# ProPrj_Usb_Hub_2026-05-05.net
KiCad netlist of a schematic drawn in EasyEDA Pro
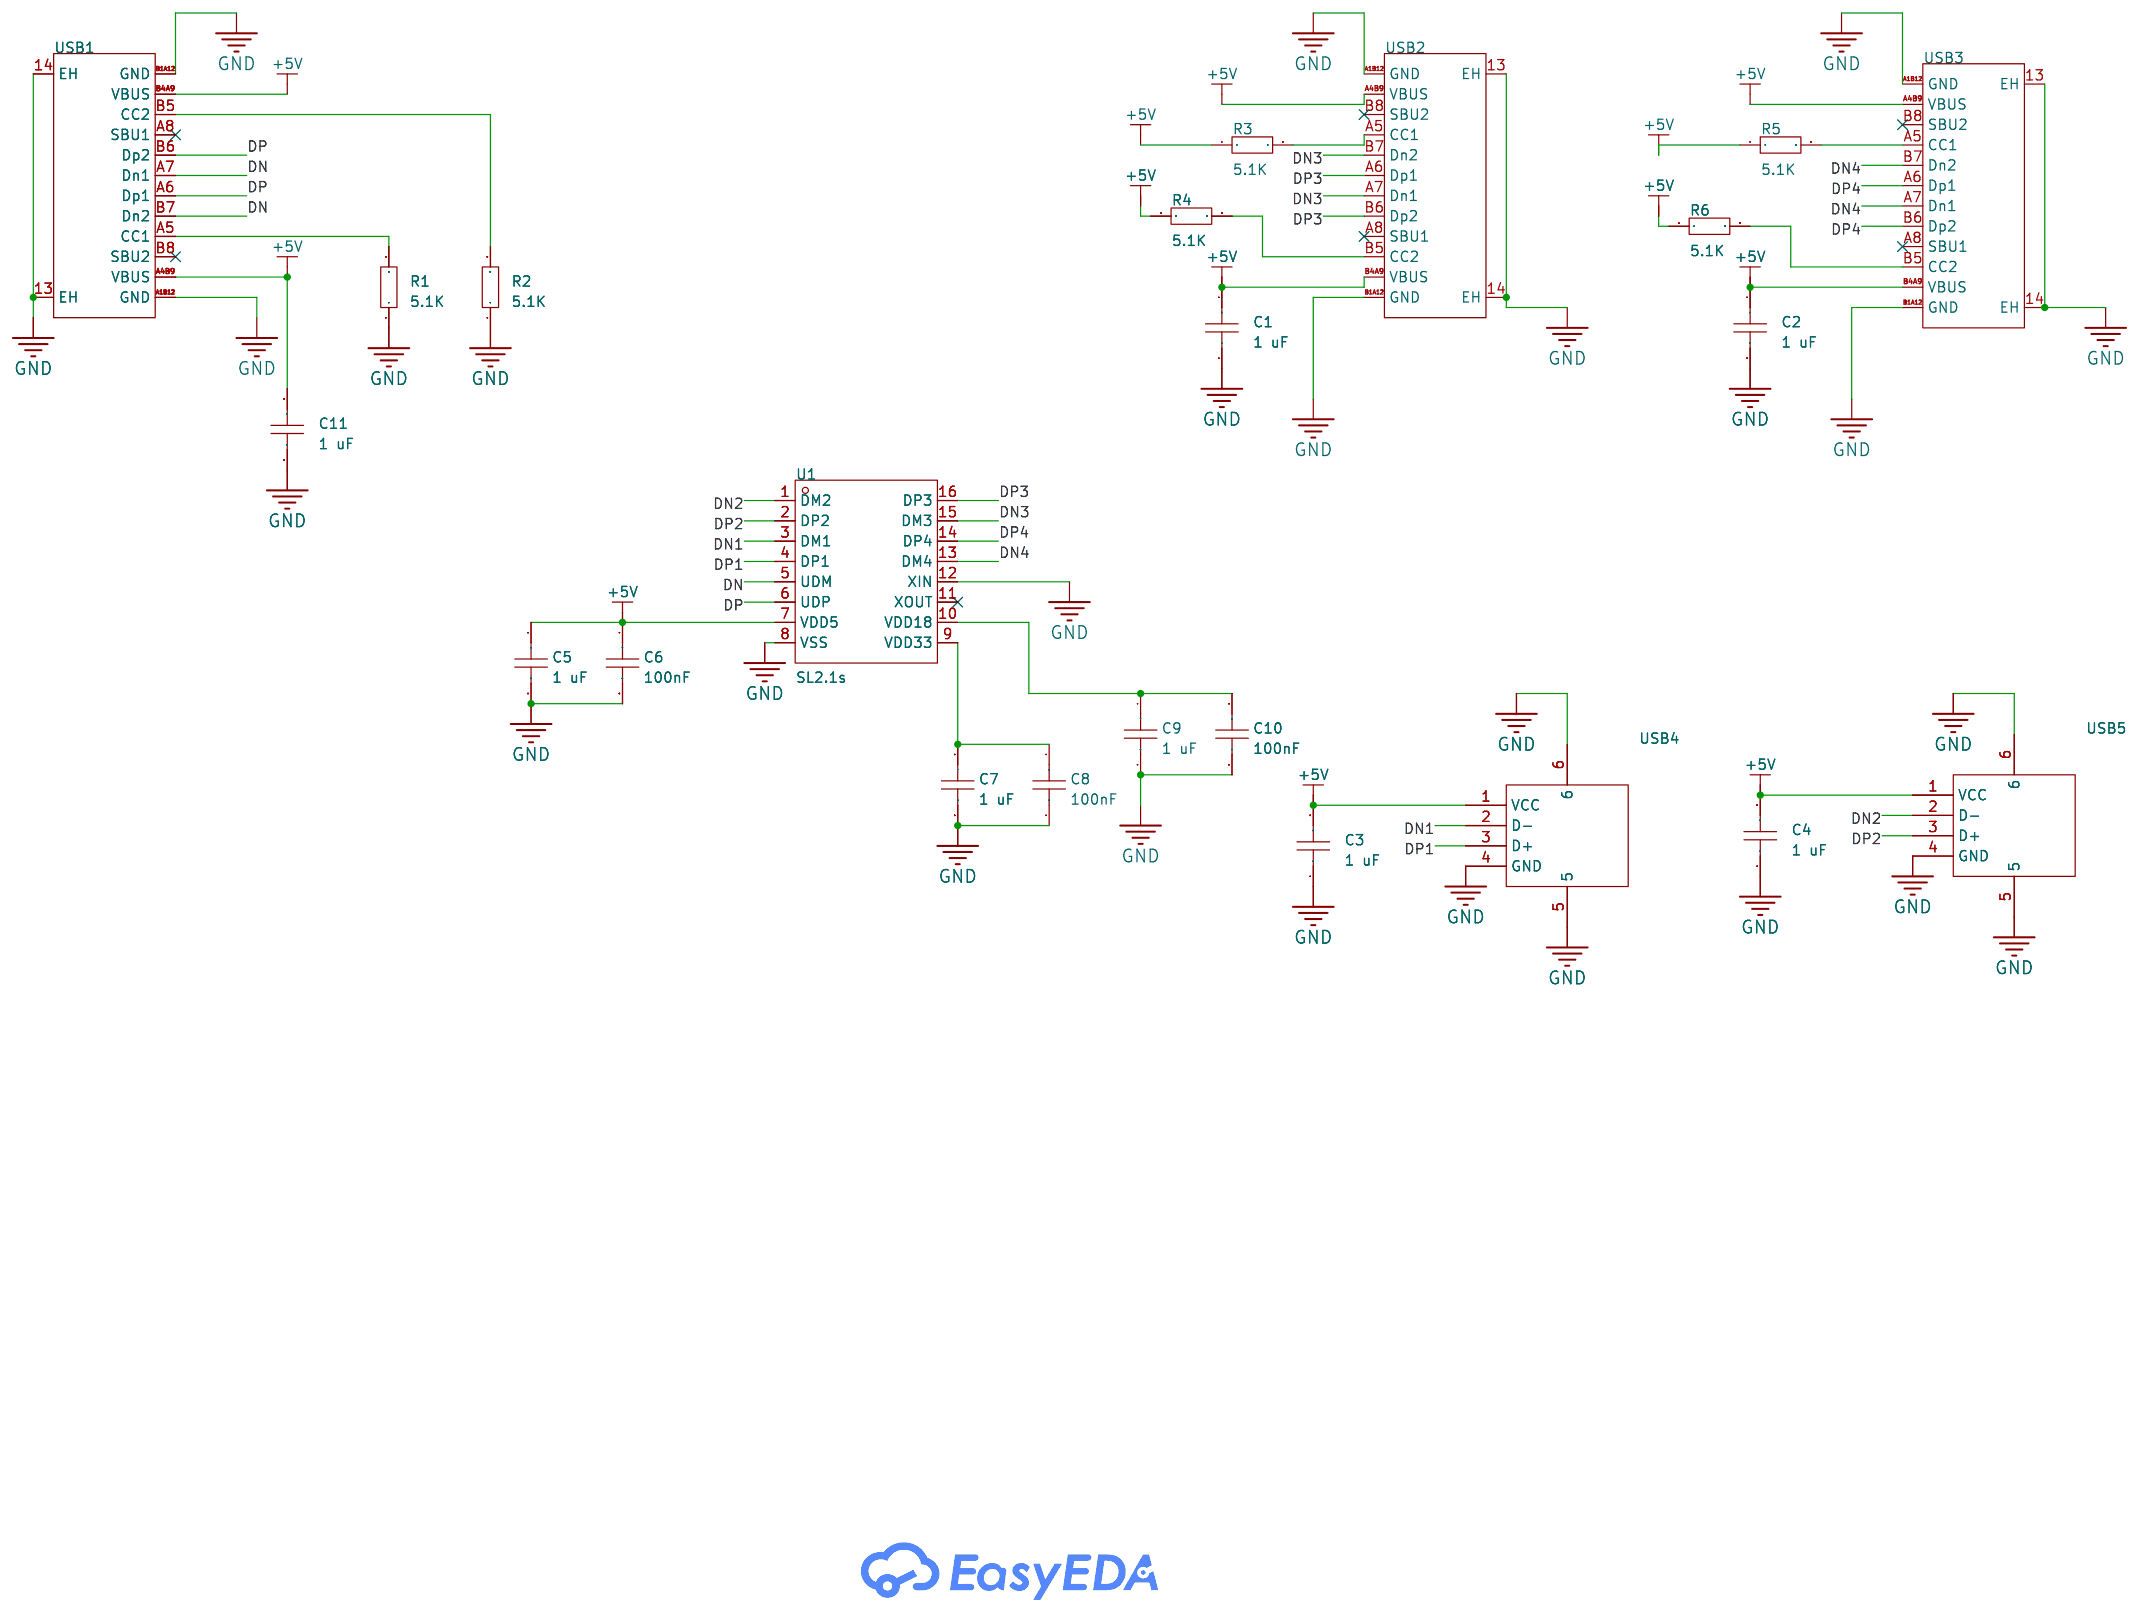
[diagram p0: schematic sheet]

(export (version "E")
  (design (tool "Eeschema 10.0.6"))
  (components
    (comp (ref "C1")
      (value "1 uF")
      (footprint "easyedapro:C0603")
      (libsource (lib "easyedapro") (part "CAP"))
    )
    (comp (ref "C2")
      (value "1 uF")
      (footprint "easyedapro:C0603")
      (libsource (lib "easyedapro") (part "CAP"))
    )
    (comp (ref "C3")
      (value "1 uF")
      (footprint "easyedapro:C0603")
      (libsource (lib "easyedapro") (part "CAP"))
    )
    (comp (ref "C4")
      (value "1 uF")
      (footprint "easyedapro:C0603")
      (libsource (lib "easyedapro") (part "CAP"))
    )
    (comp (ref "C5")
      (value "1 uF")
      (footprint "easyedapro:C0603")
      (libsource (lib "easyedapro") (part "CAP"))
    )
    (comp (ref "C6")
      (value "100nF")
      (footprint "easyedapro:C0603")
      (libsource (lib "easyedapro") (part "CAP"))
    )
    (comp (ref "C7")
      (value "1 uF")
      (footprint "easyedapro:C0603")
      (libsource (lib "easyedapro") (part "CAP"))
    )
    (comp (ref "C8")
      (value "100nF")
      (footprint "easyedapro:C0603")
      (libsource (lib "easyedapro") (part "CAP"))
    )
    (comp (ref "C9")
      (value "1 uF")
      (footprint "easyedapro:C0603")
      (libsource (lib "easyedapro") (part "CAP"))
    )
    (comp (ref "C10")
      (value "100nF")
      (footprint "easyedapro:C0603")
      (libsource (lib "easyedapro") (part "CAP"))
    )
    (comp (ref "C11")
      (value "1 uF")
      (footprint "easyedapro:C0603")
      (libsource (lib "easyedapro") (part "CAP"))
    )
    (comp (ref "R1")
      (value "5.1K")
      (footprint "easyedapro:R0603")
      (libsource (lib "easyedapro") (part "Res"))
    )
    (comp (ref "R2")
      (value "5.1K")
      (footprint "easyedapro:R0603")
      (libsource (lib "easyedapro") (part "Res"))
    )
    (comp (ref "R3")
      (value "5.1K")
      (footprint "easyedapro:R0603")
      (libsource (lib "easyedapro") (part "Res"))
    )
    (comp (ref "R4")
      (value "5.1K")
      (footprint "easyedapro:R0603")
      (libsource (lib "easyedapro") (part "Res"))
    )
    (comp (ref "R5")
      (value "5.1K")
      (footprint "easyedapro:R0603")
      (libsource (lib "easyedapro") (part "Res"))
    )
    (comp (ref "R6")
      (value "5.1K")
      (footprint "easyedapro:R0603")
      (libsource (lib "easyedapro") (part "Res"))
    )
    (comp (ref "U1")
      (value "SL2.1s")
      (footprint "easyedapro:SSOP-16_L4.6-W2.6-P0.53-LS4.0-BL")
      (fields (field (name "Manufacturer") "CoreChips(和芯润德)"))
      (libsource (lib "easyedapro") (part "SL2.1S"))
    )
    (comp (ref "USB1")
      (value "TYPE-C 16PIN 2MD(073)")
      (footprint "easyedapro:USB-C-SMD_TYPE-C-16PIN-2MD-073")
      (fields (field (name "Manufacturer") "SHOU HAN(首韩)"))
      (libsource (lib "easyedapro") (part "TYPE-C 16PIN 2MD(073)"))
    )
    (comp (ref "USB2")
      (value "TYPE-C 16PIN 2MD(073)")
      (footprint "easyedapro:USB-C-SMD_TYPE-C-16PIN-2MD-073")
      (fields (field (name "Manufacturer") "SHOU HAN(首韩)"))
      (libsource (lib "easyedapro") (part "TYPE-C 16PIN 2MD(073)"))
    )
    (comp (ref "USB3")
      (value "TYPE-C 16PIN 2MD(073)")
      (footprint "easyedapro:USB-C-SMD_TYPE-C-16PIN-2MD-073")
      (fields (field (name "Manufacturer") "SHOU HAN(首韩)"))
      (libsource (lib "easyedapro") (part "TYPE-C 16PIN 2MD(073)"))
    )
    (comp (ref "USB4")
      (value "10.0 QHHTZB6.3")
      (footprint "easyedapro:USB-A-TH_10.0QHHTZB6.3")
      (fields (field (name "Manufacturer") "SHOU HAN(首韩)"))
      (libsource (lib "easyedapro") (part "10.0 QHHTZB6.3"))
    )
    (comp (ref "USB5")
      (value "10.0 QHHTZB6.3")
      (footprint "easyedapro:USB-A-TH_10.0QHHTZB6.3")
      (fields (field (name "Manufacturer") "SHOU HAN(首韩)"))
      (libsource (lib "easyedapro") (part "10.0 QHHTZB6.3"))
    )
  )
  (nets
    (net (code "1") (name "+5V") (class "Default")
      (node (ref "C1") (pin "1") (pinfunction "1_1") (pintype "input"))
      (node (ref "C11") (pin "1") (pinfunction "1_1") (pintype "input"))
      (node (ref "C2") (pin "1") (pinfunction "1_1") (pintype "input"))
      (node (ref "C3") (pin "2") (pinfunction "2_2") (pintype "input"))
      (node (ref "C4") (pin "2") (pinfunction "2_2") (pintype "input"))
      (node (ref "C5") (pin "1") (pinfunction "1_1") (pintype "input"))
      (node (ref "C6") (pin "1") (pinfunction "1_1") (pintype "input"))
      (node (ref "R3") (pin "1") (pinfunction "1_1") (pintype "input"))
      (node (ref "R4") (pin "1") (pinfunction "1_1") (pintype "input"))
      (node (ref "R5") (pin "1") (pinfunction "1_1") (pintype "input"))
      (node (ref "R6") (pin "1") (pinfunction "1_1") (pintype "input"))
      (node (ref "U1") (pin "7") (pinfunction "VDD5_7") (pintype "unspecified"))
      (node (ref "USB1") (pin "A4B9") (pinfunction "VBUS_A4B9") (pintype "unspecified"))
      (node (ref "USB1") (pin "B4A9") (pinfunction "VBUS_B4A9") (pintype "unspecified"))
      (node (ref "USB2") (pin "A4B9") (pinfunction "VBUS_A4B9") (pintype "unspecified"))
      (node (ref "USB2") (pin "B4A9") (pinfunction "VBUS_B4A9") (pintype "unspecified"))
      (node (ref "USB3") (pin "A4B9") (pinfunction "VBUS_A4B9") (pintype "unspecified"))
      (node (ref "USB3") (pin "B4A9") (pinfunction "VBUS_B4A9") (pintype "unspecified"))
      (node (ref "USB4") (pin "1") (pinfunction "VCC_1") (pintype "unspecified"))
      (node (ref "USB5") (pin "1") (pinfunction "VCC_1") (pintype "unspecified"))
    )
    (net (code "2") (name "/DN") (class "Default")
      (node (ref "U1") (pin "5") (pinfunction "UDM_5") (pintype "unspecified"))
      (node (ref "USB1") (pin "A7") (pinfunction "Dn1_A7") (pintype "unspecified"))
      (node (ref "USB1") (pin "B7") (pinfunction "Dn2_B7") (pintype "unspecified"))
    )
    (net (code "3") (name "/DN1") (class "Default")
      (node (ref "U1") (pin "3") (pinfunction "DM1_3") (pintype "unspecified"))
      (node (ref "USB4") (pin "2") (pinfunction "D-_2") (pintype "unspecified"))
    )
    (net (code "4") (name "/DN2") (class "Default")
      (node (ref "U1") (pin "1") (pinfunction "DM2_1") (pintype "unspecified"))
      (node (ref "USB5") (pin "2") (pinfunction "D-_2") (pintype "unspecified"))
    )
    (net (code "5") (name "/DN3") (class "Default")
      (node (ref "U1") (pin "15") (pinfunction "DM3_15") (pintype "unspecified"))
      (node (ref "USB2") (pin "A7") (pinfunction "Dn1_A7") (pintype "unspecified"))
      (node (ref "USB2") (pin "B7") (pinfunction "Dn2_B7") (pintype "unspecified"))
    )
    (net (code "6") (name "/DN4") (class "Default")
      (node (ref "U1") (pin "13") (pinfunction "DM4_13") (pintype "unspecified"))
      (node (ref "USB3") (pin "A7") (pinfunction "Dn1_A7") (pintype "unspecified"))
      (node (ref "USB3") (pin "B7") (pinfunction "Dn2_B7") (pintype "unspecified"))
    )
    (net (code "7") (name "/DP") (class "Default")
      (node (ref "U1") (pin "6") (pinfunction "UDP_6") (pintype "unspecified"))
      (node (ref "USB1") (pin "A6") (pinfunction "Dp1_A6") (pintype "unspecified"))
      (node (ref "USB1") (pin "B6") (pinfunction "Dp2_B6") (pintype "unspecified"))
    )
    (net (code "8") (name "/DP1") (class "Default")
      (node (ref "U1") (pin "4") (pinfunction "DP1_4") (pintype "unspecified"))
      (node (ref "USB4") (pin "3") (pinfunction "D+_3") (pintype "unspecified"))
    )
    (net (code "9") (name "/DP2") (class "Default")
      (node (ref "U1") (pin "2") (pinfunction "DP2_2") (pintype "unspecified"))
      (node (ref "USB5") (pin "3") (pinfunction "D+_3") (pintype "unspecified"))
    )
    (net (code "10") (name "/DP3") (class "Default")
      (node (ref "U1") (pin "16") (pinfunction "DP3_16") (pintype "unspecified"))
      (node (ref "USB2") (pin "A6") (pinfunction "Dp1_A6") (pintype "unspecified"))
      (node (ref "USB2") (pin "B6") (pinfunction "Dp2_B6") (pintype "unspecified"))
    )
    (net (code "11") (name "/DP4") (class "Default")
      (node (ref "U1") (pin "14") (pinfunction "DP4_14") (pintype "unspecified"))
      (node (ref "USB3") (pin "A6") (pinfunction "Dp1_A6") (pintype "unspecified"))
      (node (ref "USB3") (pin "B6") (pinfunction "Dp2_B6") (pintype "unspecified"))
    )
    (net (code "12") (name "GND") (class "Default")
      (node (ref "C1") (pin "2") (pinfunction "2_2") (pintype "input"))
      (node (ref "C10") (pin "2") (pinfunction "2_2") (pintype "input"))
      (node (ref "C11") (pin "2") (pinfunction "2_2") (pintype "input"))
      (node (ref "C2") (pin "2") (pinfunction "2_2") (pintype "input"))
      (node (ref "C3") (pin "1") (pinfunction "1_1") (pintype "input"))
      (node (ref "C4") (pin "1") (pinfunction "1_1") (pintype "input"))
      (node (ref "C5") (pin "2") (pinfunction "2_2") (pintype "input"))
      (node (ref "C6") (pin "2") (pinfunction "2_2") (pintype "input"))
      (node (ref "C7") (pin "2") (pinfunction "2_2") (pintype "input"))
      (node (ref "C8") (pin "2") (pinfunction "2_2") (pintype "input"))
      (node (ref "C9") (pin "2") (pinfunction "2_2") (pintype "input"))
      (node (ref "R1") (pin "1") (pinfunction "1_1") (pintype "input"))
      (node (ref "R2") (pin "1") (pinfunction "1_1") (pintype "input"))
      (node (ref "U1") (pin "12") (pinfunction "XIN_12") (pintype "unspecified"))
      (node (ref "U1") (pin "8") (pinfunction "VSS_8") (pintype "unspecified"))
      (node (ref "USB1") (pin "13") (pinfunction "EH_13") (pintype "unspecified"))
      (node (ref "USB1") (pin "14") (pinfunction "EH_14") (pintype "unspecified"))
      (node (ref "USB1") (pin "A1B12") (pinfunction "GND_A1B12") (pintype "unspecified"))
      (node (ref "USB1") (pin "B1A12") (pinfunction "GND_B1A12") (pintype "unspecified"))
      (node (ref "USB2") (pin "13") (pinfunction "EH_13") (pintype "unspecified"))
      (node (ref "USB2") (pin "14") (pinfunction "EH_14") (pintype "unspecified"))
      (node (ref "USB2") (pin "A1B12") (pinfunction "GND_A1B12") (pintype "unspecified"))
      (node (ref "USB2") (pin "B1A12") (pinfunction "GND_B1A12") (pintype "unspecified"))
      (node (ref "USB3") (pin "13") (pinfunction "EH_13") (pintype "unspecified"))
      (node (ref "USB3") (pin "14") (pinfunction "EH_14") (pintype "unspecified"))
      (node (ref "USB3") (pin "A1B12") (pinfunction "GND_A1B12") (pintype "unspecified"))
      (node (ref "USB3") (pin "B1A12") (pinfunction "GND_B1A12") (pintype "unspecified"))
      (node (ref "USB4") (pin "4") (pinfunction "GND_4") (pintype "unspecified"))
      (node (ref "USB4") (pin "5") (pinfunction "5_5") (pintype "unspecified"))
      (node (ref "USB4") (pin "6") (pinfunction "6_6") (pintype "unspecified"))
      (node (ref "USB5") (pin "4") (pinfunction "GND_4") (pintype "unspecified"))
      (node (ref "USB5") (pin "5") (pinfunction "5_5") (pintype "unspecified"))
      (node (ref "USB5") (pin "6") (pinfunction "6_6") (pintype "unspecified"))
    )
    (net (code "13") (name "Net-(U1-VDD18)") (class "Default")
      (node (ref "C10") (pin "1") (pinfunction "1_1") (pintype "input"))
      (node (ref "C9") (pin "1") (pinfunction "1_1") (pintype "input"))
      (node (ref "U1") (pin "10") (pinfunction "VDD18_10") (pintype "unspecified"))
    )
    (net (code "14") (name "Net-(U1-VDD33)") (class "Default")
      (node (ref "C7") (pin "1") (pinfunction "1_1") (pintype "input"))
      (node (ref "C8") (pin "1") (pinfunction "1_1") (pintype "input"))
      (node (ref "U1") (pin "9") (pinfunction "VDD33_9") (pintype "unspecified"))
    )
    (net (code "15") (name "Net-(USB1-CC1)") (class "Default")
      (node (ref "R1") (pin "2") (pinfunction "2_2") (pintype "input"))
      (node (ref "USB1") (pin "A5") (pinfunction "CC1_A5") (pintype "unspecified"))
    )
    (net (code "16") (name "Net-(USB1-CC2)") (class "Default")
      (node (ref "R2") (pin "2") (pinfunction "2_2") (pintype "input"))
      (node (ref "USB1") (pin "B5") (pinfunction "CC2_B5") (pintype "unspecified"))
    )
    (net (code "17") (name "Net-(USB2-CC1)") (class "Default")
      (node (ref "R3") (pin "2") (pinfunction "2_2") (pintype "input"))
      (node (ref "USB2") (pin "A5") (pinfunction "CC1_A5") (pintype "unspecified"))
    )
    (net (code "18") (name "Net-(USB2-CC2)") (class "Default")
      (node (ref "R4") (pin "2") (pinfunction "2_2") (pintype "input"))
      (node (ref "USB2") (pin "B5") (pinfunction "CC2_B5") (pintype "unspecified"))
    )
    (net (code "19") (name "Net-(USB3-CC1)") (class "Default")
      (node (ref "R5") (pin "2") (pinfunction "2_2") (pintype "input"))
      (node (ref "USB3") (pin "A5") (pinfunction "CC1_A5") (pintype "unspecified"))
    )
    (net (code "20") (name "Net-(USB3-CC2)") (class "Default")
      (node (ref "R6") (pin "2") (pinfunction "2_2") (pintype "input"))
      (node (ref "USB3") (pin "B5") (pinfunction "CC2_B5") (pintype "unspecified"))
    )
    (net (code "21") (name "unconnected-(U1-XOUT-Pad11)") (class "Default")
      (node (ref "U1") (pin "11") (pinfunction "XOUT_11") (pintype "unspecified+no_connect"))
    )
    (net (code "22") (name "unconnected-(USB1-SBU1-PadA8)") (class "Default")
      (node (ref "USB1") (pin "A8") (pinfunction "SBU1_A8") (pintype "unspecified+no_connect"))
    )
    (net (code "23") (name "unconnected-(USB1-SBU2-PadB8)") (class "Default")
      (node (ref "USB1") (pin "B8") (pinfunction "SBU2_B8") (pintype "unspecified+no_connect"))
    )
    (net (code "24") (name "unconnected-(USB2-SBU1-PadA8)") (class "Default")
      (node (ref "USB2") (pin "A8") (pinfunction "SBU1_A8") (pintype "unspecified+no_connect"))
    )
    (net (code "25") (name "unconnected-(USB2-SBU2-PadB8)") (class "Default")
      (node (ref "USB2") (pin "B8") (pinfunction "SBU2_B8") (pintype "unspecified+no_connect"))
    )
    (net (code "26") (name "unconnected-(USB3-SBU1-PadA8)") (class "Default")
      (node (ref "USB3") (pin "A8") (pinfunction "SBU1_A8") (pintype "unspecified+no_connect"))
    )
    (net (code "27") (name "unconnected-(USB3-SBU2-PadB8)") (class "Default")
      (node (ref "USB3") (pin "B8") (pinfunction "SBU2_B8") (pintype "unspecified+no_connect"))
    )
  )
)
